# V1.net
KiCad netlist of a schematic drawn in Altium Designer
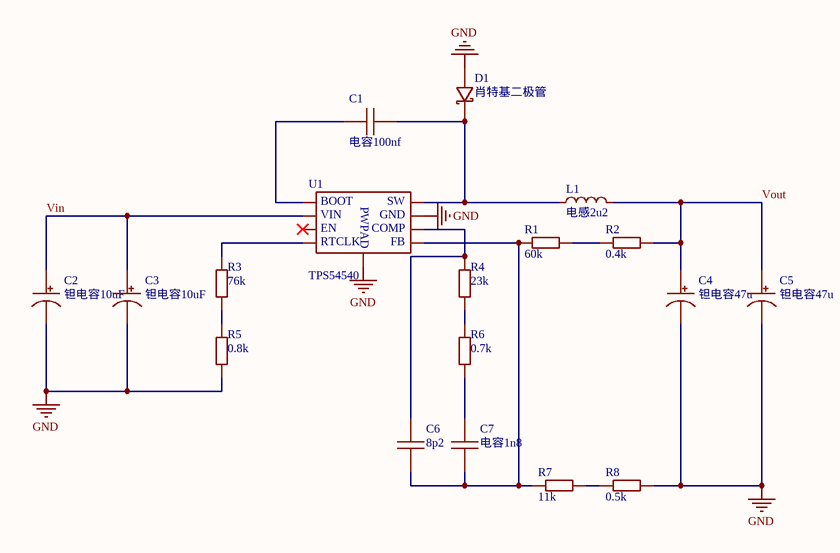
[diagram p0: V1.SchDoc]

(export (version "E")
  (design (tool "Eeschema 10.0.6"))
  (components
    (comp (ref "C1") (value "电容100nf") (footprint "0603C") (libsource (lib "元件库") (part "电容_贴片")))
    (comp (ref "C2") (value "钽电容10uF") (footprint "3528B/1210") (libsource (lib "元件库") (part "电容_贴片钽")))
    (comp (ref "C3") (value "钽电容10uF") (footprint "3528B/1210") (libsource (lib "元件库") (part "电容_贴片钽")))
    (comp (ref "C4") (value "钽电容47u") (footprint "3528B/1210") (libsource (lib "元件库") (part "电容_贴片钽")))
    (comp (ref "C5") (value "钽电容47u") (footprint "3528B/1210") (libsource (lib "元件库") (part "电容_贴片钽")))
    (comp (ref "C6") (value "8p2") (footprint "0603C") (libsource (lib "元件库") (part "电容_贴片")))
    (comp (ref "C7") (value "电容1n8") (footprint "0603C") (libsource (lib "元件库") (part "电容_贴片")))
    (comp (ref "D1") (value "肖特基二极管") (footprint "SMA") (libsource (lib "元件库") (part "二极管_肖特基")))
    (comp (ref "L1") (value "电感2u2") (footprint "CD7X") (libsource (lib "元件库") (part "电感_贴片")))
    (comp (ref "R1") (value "60k") (footprint "0603R") (libsource (lib "元件库") (part "电阻_贴片")))
    (comp (ref "R2") (value "0.4k") (footprint "0603R") (libsource (lib "元件库") (part "电阻_贴片")))
    (comp (ref "R3") (value "76k") (footprint "0603R") (libsource (lib "") (part "电阻_贴片_1")))
    (comp (ref "R4") (value "23k") (footprint "0603R") (libsource (lib "") (part "电阻_贴片_1")))
    (comp (ref "R5") (value "0.8k") (footprint "0603R") (libsource (lib "") (part "电阻_贴片_1")))
    (comp (ref "R6") (value "0.7k") (footprint "0603R") (libsource (lib "") (part "电阻_贴片_1")))
    (comp (ref "R7") (value "11k") (footprint "0603R") (libsource (lib "元件库") (part "电阻_贴片")))
    (comp (ref "R8") (value "0.5k") (footprint "0603R") (libsource (lib "元件库") (part "电阻_贴片")))
    (comp (ref "U1")
      (value "TPS54540")
      (footprint "SOP-8-PP")
      (libsource (lib "元件库") (part "芯片/IC-TPS54540"))
    )
  )
  (nets
    (net (code "1") (name "/Vin") (class "Default")
      (node (ref "C2") (pin "1") (pinfunction "1_1") (pintype "passive"))
      (node (ref "C3") (pin "1") (pinfunction "1_1") (pintype "passive"))
      (node (ref "U1") (pin "2") (pinfunction "2_2") (pintype "passive"))
    )
    (net (code "2") (name "/Vout") (class "Default")
      (node (ref "C4") (pin "1") (pinfunction "1_1") (pintype "passive"))
      (node (ref "C5") (pin "1") (pinfunction "1_1") (pintype "passive"))
      (node (ref "L1") (pin "2") (pinfunction "2_2") (pintype "passive"))
      (node (ref "R2") (pin "2") (pinfunction "2_2") (pintype "passive"))
    )
    (net (code "3") (name "GND") (class "Default")
      (node (ref "C2") (pin "2") (pinfunction "2_2") (pintype "passive"))
      (node (ref "C3") (pin "2") (pinfunction "2_2") (pintype "passive"))
      (node (ref "C4") (pin "2") (pinfunction "2_2") (pintype "passive"))
      (node (ref "C5") (pin "2") (pinfunction "2_2") (pintype "passive"))
      (node (ref "D1") (pin "1") (pinfunction "1_1") (pintype "passive"))
      (node (ref "R5") (pin "1") (pinfunction "1_1") (pintype "passive"))
      (node (ref "R8") (pin "2") (pinfunction "2_2") (pintype "passive"))
      (node (ref "U1") (pin "7") (pinfunction "7_7") (pintype "passive"))
      (node (ref "U1") (pin "9") (pinfunction "9_9") (pintype "passive"))
    )
    (net (code "4") (name "Net-(C1-Pad1)") (class "Default")
      (node (ref "C1") (pin "1") (pinfunction "1_1") (pintype "passive"))
      (node (ref "U1") (pin "1") (pinfunction "1_1") (pintype "passive"))
    )
    (net (code "5") (name "Net-(C1-Pad2)") (class "Default")
      (node (ref "C1") (pin "2") (pinfunction "2_2") (pintype "passive"))
      (node (ref "D1") (pin "2") (pinfunction "2_2") (pintype "passive"))
      (node (ref "L1") (pin "1") (pinfunction "1_1") (pintype "passive"))
      (node (ref "U1") (pin "8") (pinfunction "8_8") (pintype "passive"))
    )
    (net (code "6") (name "Net-(C6-Pad1)") (class "Default")
      (node (ref "C6") (pin "1") (pinfunction "1_1") (pintype "passive"))
      (node (ref "R4") (pin "2") (pinfunction "2_2") (pintype "passive"))
      (node (ref "U1") (pin "6") (pinfunction "6_6") (pintype "passive"))
    )
    (net (code "7") (name "Net-(C6-Pad2)") (class "Default")
      (node (ref "C6") (pin "2") (pinfunction "2_2") (pintype "passive"))
      (node (ref "C7") (pin "2") (pinfunction "2_2") (pintype "passive"))
      (node (ref "R1") (pin "1") (pinfunction "1_1") (pintype "passive"))
      (node (ref "R7") (pin "1") (pinfunction "1_1") (pintype "passive"))
      (node (ref "U1") (pin "5") (pinfunction "5_5") (pintype "passive"))
    )
    (net (code "8") (name "Net-(C7-Pad1)") (class "Default")
      (node (ref "C7") (pin "1") (pinfunction "1_1") (pintype "passive"))
      (node (ref "R6") (pin "1") (pinfunction "1_1") (pintype "passive"))
    )
    (net (code "9") (name "Net-(R1-Pad2)") (class "Default")
      (node (ref "R1") (pin "2") (pinfunction "2_2") (pintype "passive"))
      (node (ref "R2") (pin "1") (pinfunction "1_1") (pintype "passive"))
    )
    (net (code "10") (name "Net-(R3-Pad1)") (class "Default")
      (node (ref "R3") (pin "1") (pinfunction "1_1") (pintype "passive"))
      (node (ref "R5") (pin "2") (pinfunction "2_2") (pintype "passive"))
    )
    (net (code "11") (name "Net-(R3-Pad2)") (class "Default")
      (node (ref "R3") (pin "2") (pinfunction "2_2") (pintype "passive"))
      (node (ref "U1") (pin "4") (pinfunction "4_4") (pintype "passive"))
    )
    (net (code "12") (name "Net-(R4-Pad1)") (class "Default")
      (node (ref "R4") (pin "1") (pinfunction "1_1") (pintype "passive"))
      (node (ref "R6") (pin "2") (pinfunction "2_2") (pintype "passive"))
    )
    (net (code "13") (name "Net-(R7-Pad2)") (class "Default")
      (node (ref "R7") (pin "2") (pinfunction "2_2") (pintype "passive"))
      (node (ref "R8") (pin "1") (pinfunction "1_1") (pintype "passive"))
    )
    (net (code "14") (name "unconnected-(U1-Pad3)") (class "Default")
      (node (ref "U1") (pin "3") (pinfunction "3_3") (pintype "passive+no_connect"))
    )
  )
)
